# lens.net
KiCad netlist of a schematic drawn in EAGLE
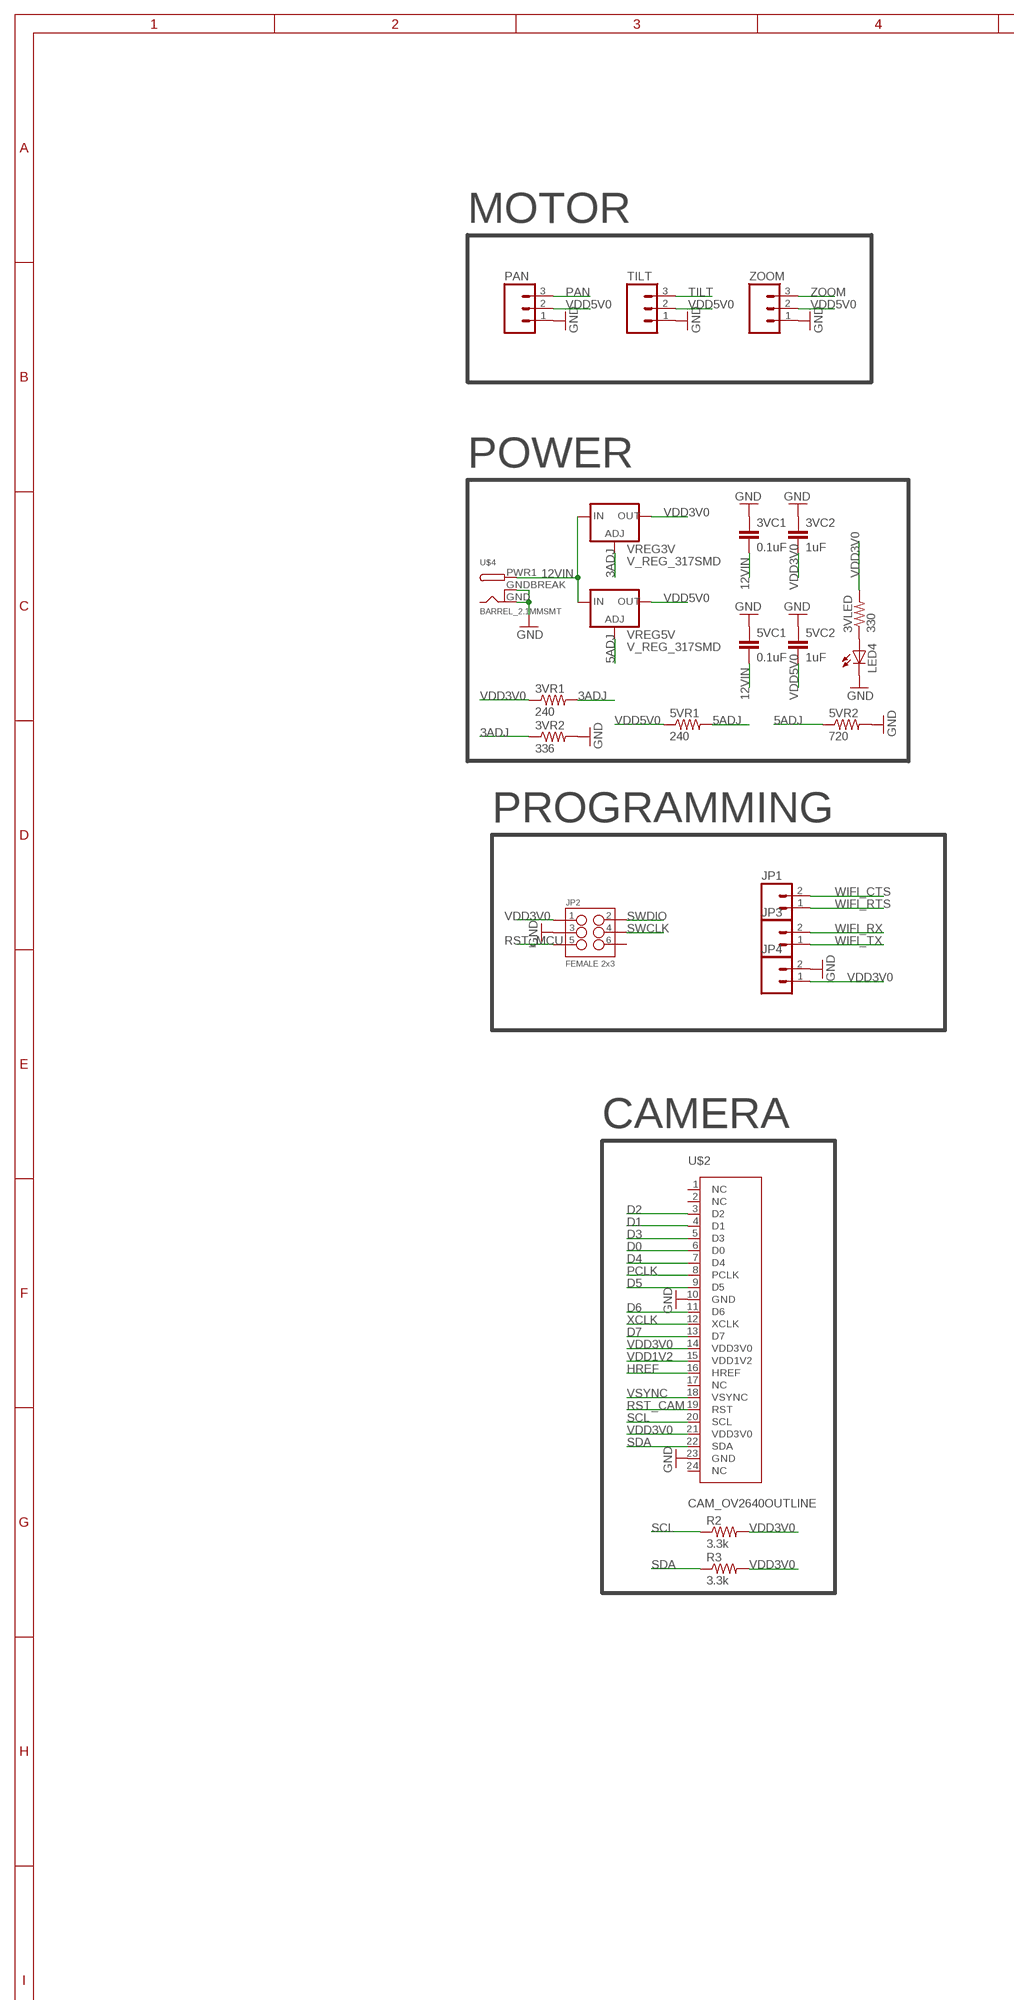
[diagram p0: schematic, sheet 1, part 1 of 2]
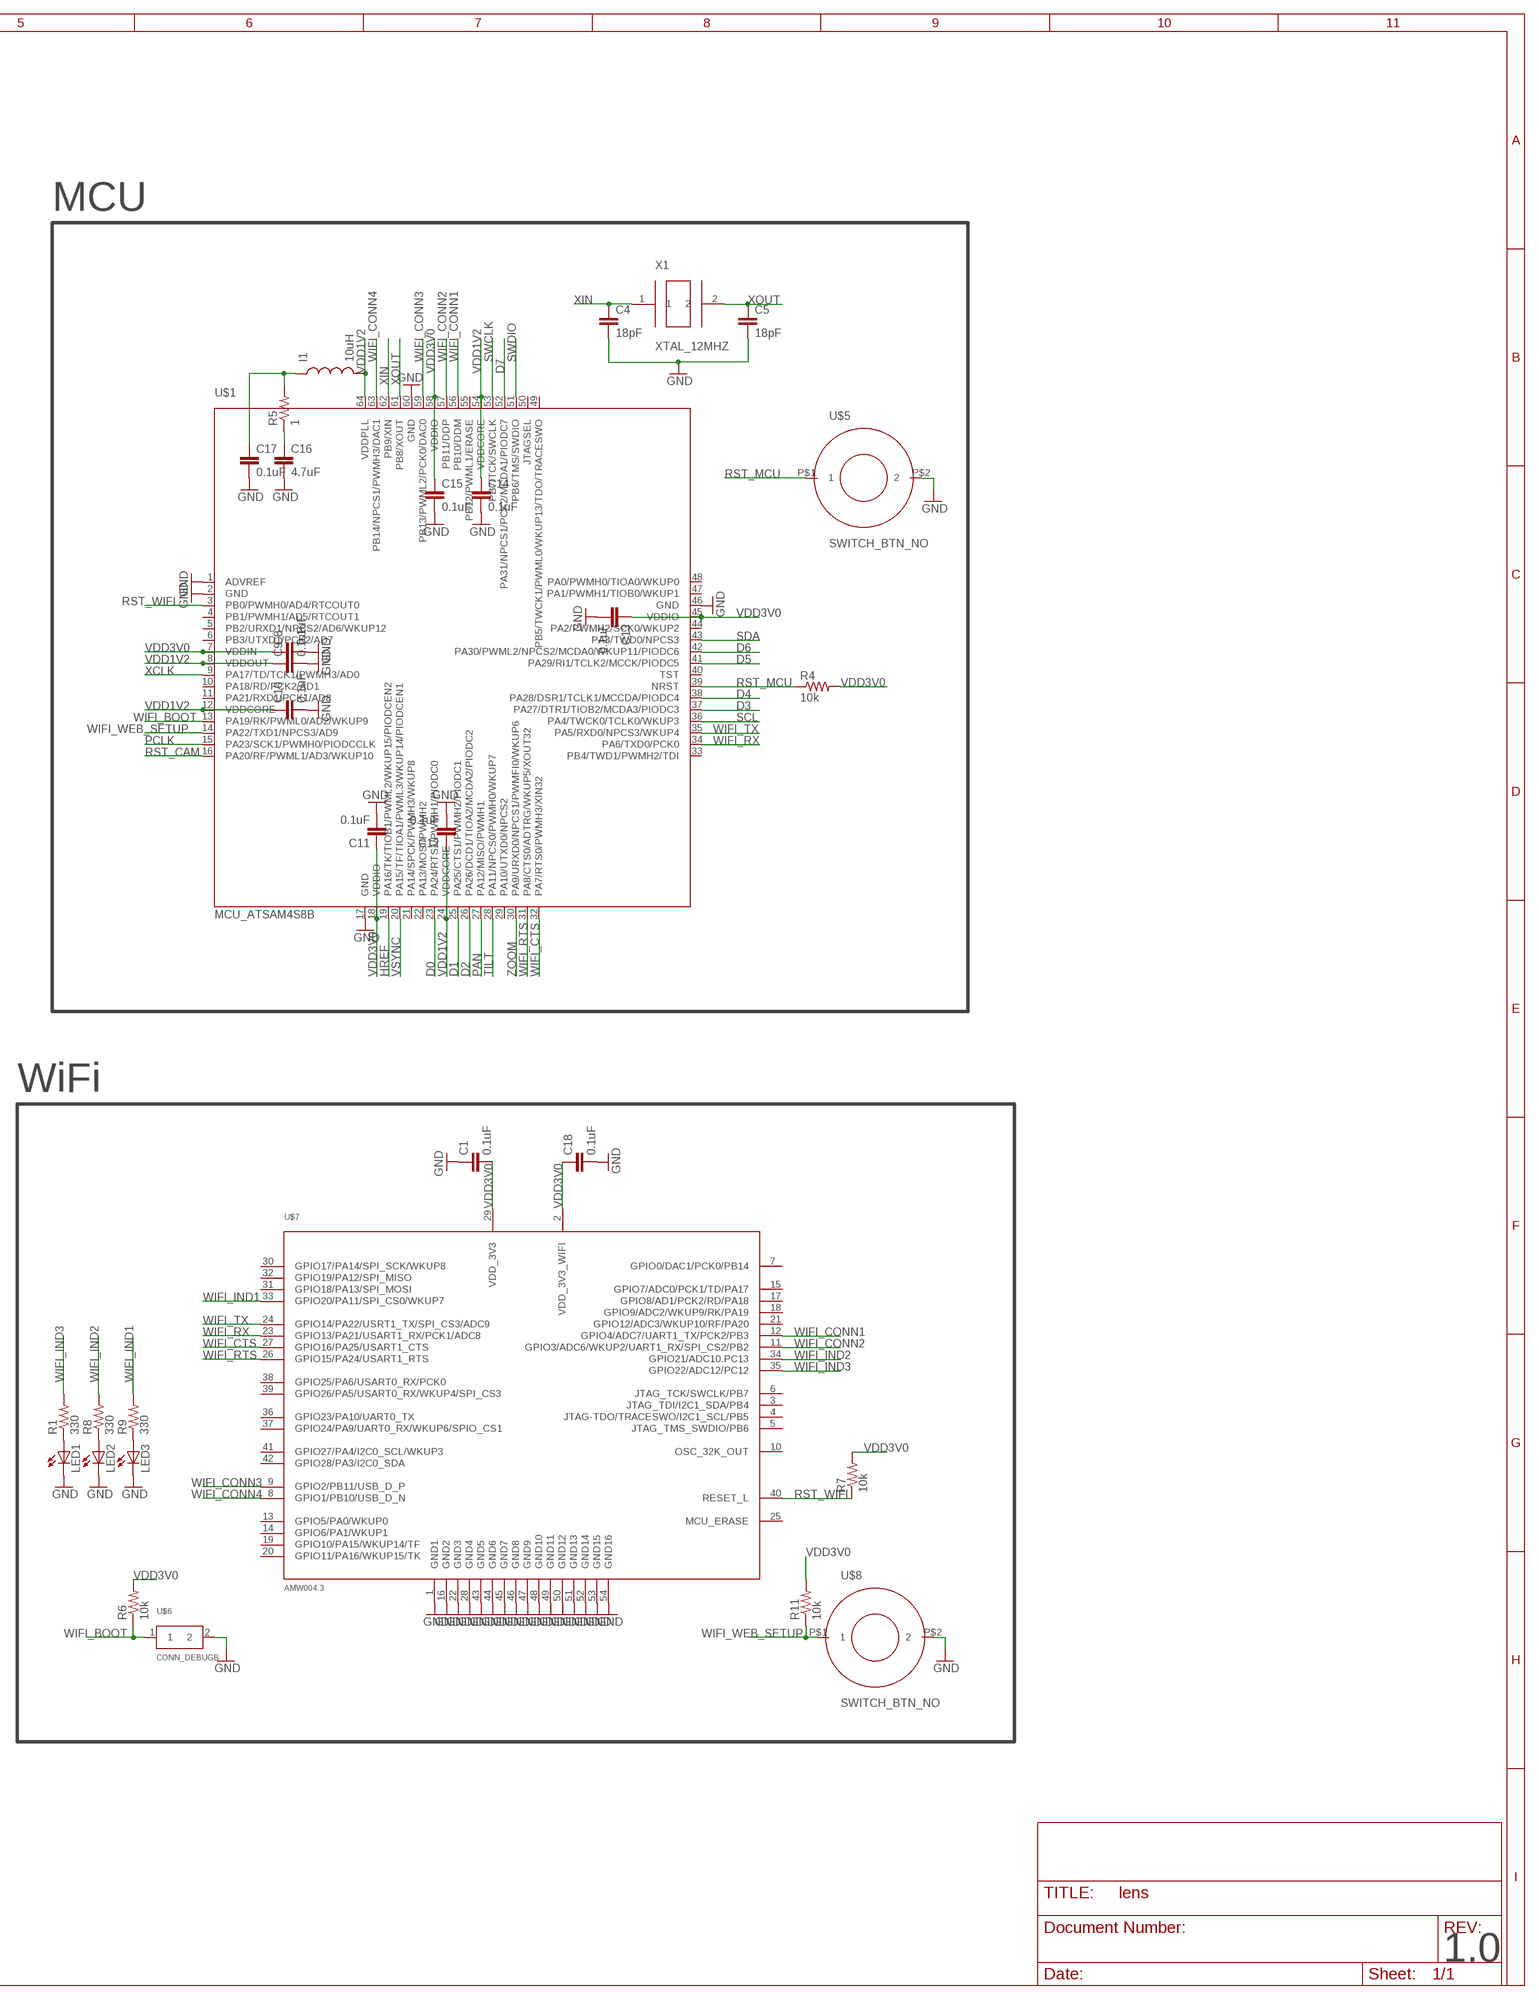
[diagram p1: schematic, sheet 1, part 2 of 2]

(export (version "E")
  (design (tool "Eeschema 10.0.6"))
  (components
    (comp (ref "3VC1")
      (value "0.1uF")
      (footprint "eagle-import:0805")
      (libsource (lib "eagle-import") (part "CAP"))
    )
    (comp (ref "3VC2")
      (value "1uF")
      (footprint "eagle-import:0805")
      (libsource (lib "eagle-import") (part "CAP"))
    )
    (comp (ref "3VLED")
      (value "330")
      (footprint "eagle-import:0805")
      (libsource (lib "eagle-import") (part "RES"))
    )
    (comp (ref "3VR1")
      (value "240")
      (footprint "eagle-import:0805")
      (libsource (lib "eagle-import") (part "RES"))
    )
    (comp (ref "3VR2")
      (value "336")
      (footprint "eagle-import:0805")
      (libsource (lib "eagle-import") (part "RES"))
    )
    (comp (ref "5VC1")
      (value "0.1uF")
      (footprint "eagle-import:0805")
      (libsource (lib "eagle-import") (part "CAP"))
    )
    (comp (ref "5VC2")
      (value "1uF")
      (footprint "eagle-import:0805")
      (libsource (lib "eagle-import") (part "CAP"))
    )
    (comp (ref "5VR1")
      (value "240")
      (footprint "eagle-import:0805")
      (libsource (lib "eagle-import") (part "RES"))
    )
    (comp (ref "5VR2")
      (value "720")
      (footprint "eagle-import:0805")
      (libsource (lib "eagle-import") (part "RES"))
    )
    (comp (ref "C1")
      (value "0.1uF")
      (footprint "eagle-import:0805")
      (libsource (lib "eagle-import") (part "CAP"))
    )
    (comp (ref "C4")
      (value "18pF")
      (footprint "eagle-import:0805")
      (libsource (lib "eagle-import") (part "CAP"))
    )
    (comp (ref "C5")
      (value "18pF")
      (footprint "eagle-import:0805")
      (libsource (lib "eagle-import") (part "CAP"))
    )
    (comp (ref "C8")
      (value "0.1uF")
      (footprint "eagle-import:0805")
      (libsource (lib "eagle-import") (part "CAP"))
    )
    (comp (ref "C9")
      (value "0.1uF")
      (footprint "eagle-import:0805")
      (libsource (lib "eagle-import") (part "CAP"))
    )
    (comp (ref "C10")
      (value "0.1uF")
      (footprint "eagle-import:0805")
      (libsource (lib "eagle-import") (part "CAP"))
    )
    (comp (ref "C11")
      (value "0.1uF")
      (footprint "eagle-import:0805")
      (libsource (lib "eagle-import") (part "CAP"))
    )
    (comp (ref "C12")
      (value "0.1uF")
      (footprint "eagle-import:0805")
      (libsource (lib "eagle-import") (part "CAP"))
    )
    (comp (ref "C13")
      (value "0.1uF")
      (footprint "eagle-import:0805")
      (libsource (lib "eagle-import") (part "CAP"))
    )
    (comp (ref "C14")
      (value "0.1uF")
      (footprint "eagle-import:0805")
      (libsource (lib "eagle-import") (part "CAP"))
    )
    (comp (ref "C15")
      (value "0.1uF")
      (footprint "eagle-import:0805")
      (libsource (lib "eagle-import") (part "CAP"))
    )
    (comp (ref "C16")
      (value "4.7uF")
      (footprint "eagle-import:0805")
      (libsource (lib "eagle-import") (part "CAP"))
    )
    (comp (ref "C17")
      (value "0.1uF")
      (footprint "eagle-import:0805")
      (libsource (lib "eagle-import") (part "CAP"))
    )
    (comp (ref "C18")
      (value "0.1uF")
      (footprint "eagle-import:0805")
      (libsource (lib "eagle-import") (part "CAP"))
    )
    (comp (ref "I1")
      (value "10uH")
      (footprint "eagle-import:0805")
      (libsource (lib "eagle-import") (part "IND"))
    )
    (comp (ref "JP1")
      (value "M02PTH")
      (footprint "eagle-import:1X02")
      (libsource (lib "eagle-import") (part "M02PTH"))
    )
    (comp (ref "JP2")
      (value "FEMALE 2x3")
      (footprint "eagle-import:2X3")
      (libsource (lib "eagle-import") (part "M03X2FEMALE"))
    )
    (comp (ref "JP3")
      (value "M02PTH")
      (footprint "eagle-import:1X02")
      (libsource (lib "eagle-import") (part "M02PTH"))
    )
    (comp (ref "JP4")
      (value "M02PTH")
      (footprint "eagle-import:1X02")
      (libsource (lib "eagle-import") (part "M02PTH"))
    )
    (comp (ref "LED1")
      (value "LED0603")
      (footprint "eagle-import:LED-0603")
      (libsource (lib "eagle-import") (part "LED0603"))
    )
    (comp (ref "LED2")
      (value "LED0603")
      (footprint "eagle-import:LED-0603")
      (libsource (lib "eagle-import") (part "LED0603"))
    )
    (comp (ref "LED3")
      (value "LED0603")
      (footprint "eagle-import:LED-0603")
      (libsource (lib "eagle-import") (part "LED0603"))
    )
    (comp (ref "LED4")
      (value "LED0603")
      (footprint "eagle-import:LED-0603")
      (libsource (lib "eagle-import") (part "LED0603"))
    )
    (comp (ref "PAN")
      (value "M03PTH")
      (footprint "eagle-import:1X03")
      (libsource (lib "eagle-import") (part "M03PTH"))
    )
    (comp (ref "R1")
      (value "330")
      (footprint "eagle-import:0805")
      (libsource (lib "eagle-import") (part "RES"))
    )
    (comp (ref "R2")
      (value "3.3k")
      (footprint "eagle-import:0805")
      (libsource (lib "eagle-import") (part "RES"))
    )
    (comp (ref "R3")
      (value "3.3k")
      (footprint "eagle-import:0805")
      (libsource (lib "eagle-import") (part "RES"))
    )
    (comp (ref "R4")
      (value "10k")
      (footprint "eagle-import:0805")
      (libsource (lib "eagle-import") (part "RES"))
    )
    (comp (ref "R5")
      (value "1")
      (footprint "eagle-import:0805")
      (libsource (lib "eagle-import") (part "RES"))
    )
    (comp (ref "R6")
      (value "10k")
      (footprint "eagle-import:0805")
      (libsource (lib "eagle-import") (part "RES"))
    )
    (comp (ref "R7")
      (value "10k")
      (footprint "eagle-import:0805")
      (libsource (lib "eagle-import") (part "RES"))
    )
    (comp (ref "R8")
      (value "330")
      (footprint "eagle-import:0805")
      (libsource (lib "eagle-import") (part "RES"))
    )
    (comp (ref "R9")
      (value "330")
      (footprint "eagle-import:0805")
      (libsource (lib "eagle-import") (part "RES"))
    )
    (comp (ref "R11")
      (value "10k")
      (footprint "eagle-import:0805")
      (libsource (lib "eagle-import") (part "RES"))
    )
    (comp (ref "TILT")
      (value "M03PTH")
      (footprint "eagle-import:1X03")
      (libsource (lib "eagle-import") (part "M03PTH"))
    )
    (comp (ref "U$1")
      (value "MCU_ATSAM4S8B")
      (footprint "eagle-import:QFP50P1200X1200X160-64N")
      (libsource (lib "eagle-import") (part "MCU_ATSAM4S8B"))
    )
    (comp (ref "U$2")
      (value "CAM_OV2640OUTLINE")
      (footprint "eagle-import:CAM_CONN")
      (libsource (lib "eagle-import") (part "CAM_OV2640OUTLINE"))
    )
    (comp (ref "U$4")
      (value "BARREL_2.1MMSMT")
      (footprint "eagle-import:DCJACK_2MM_SMT")
      (libsource (lib "eagle-import") (part "BARREL_2.1MMSMT"))
    )
    (comp (ref "U$5")
      (value "SWITCH_BTN_NO")
      (footprint "eagle-import:BTN_2")
      (libsource (lib "eagle-import") (part "SWITCH_BTN_NO"))
    )
    (comp (ref "U$6")
      (value "CONN_DEBUGB")
      (footprint "eagle-import:1X2_SMALL_SMD")
      (libsource (lib "eagle-import") (part "CONN_DEBUGB"))
    )
    (comp (ref "U$7")
      (value "AMW004.3")
      (footprint "eagle-import:AMW004")
      (libsource (lib "eagle-import") (part "AMW004.3"))
    )
    (comp (ref "U$8")
      (value "SWITCH_BTN_NO")
      (footprint "eagle-import:BTN_2")
      (libsource (lib "eagle-import") (part "SWITCH_BTN_NO"))
    )
    (comp (ref "VREG3V")
      (value "V_REG_317SMD")
      (footprint "eagle-import:SOT223")
      (libsource (lib "eagle-import") (part "V_REG_317SMD"))
    )
    (comp (ref "VREG5V")
      (value "V_REG_317SMD")
      (footprint "eagle-import:SOT223")
      (libsource (lib "eagle-import") (part "V_REG_317SMD"))
    )
    (comp (ref "X1")
      (value "XTAL_12MHZ")
      (footprint "eagle-import:ABM7-16.000MHZ-D2Y-T")
      (libsource (lib "eagle-import") (part "XTAL_12MHZ"))
    )
    (comp (ref "ZOOM")
      (value "M03PTH")
      (footprint "eagle-import:1X03")
      (libsource (lib "eagle-import") (part "M03PTH"))
    )
  )
  (nets
    (net (code "1") (name "/3ADJ") (class "Default")
      (node (ref "3VR1") (pin "2") (pinfunction "2_2") (pintype "passive"))
      (node (ref "3VR2") (pin "1") (pinfunction "1_1") (pintype "passive"))
      (node (ref "VREG3V") (pin "1") (pinfunction "ADJ_1") (pintype "input"))
    )
    (net (code "2") (name "/5ADJ") (class "Default")
      (node (ref "5VR1") (pin "2") (pinfunction "2_2") (pintype "passive"))
      (node (ref "5VR2") (pin "1") (pinfunction "1_1") (pintype "passive"))
      (node (ref "VREG5V") (pin "1") (pinfunction "ADJ_1") (pintype "input"))
    )
    (net (code "3") (name "/12VIN") (class "Default")
      (node (ref "3VC1") (pin "2") (pinfunction "2_2") (pintype "passive"))
      (node (ref "5VC1") (pin "2") (pinfunction "2_2") (pintype "passive"))
      (node (ref "U$4") (pin "PWR1") (pinfunction "PWR_PWR1") (pintype "power_in"))
      (node (ref "VREG3V") (pin "3") (pinfunction "IN_3") (pintype "input"))
      (node (ref "VREG5V") (pin "3") (pinfunction "IN_3") (pintype "input"))
    )
    (net (code "4") (name "/D0") (class "Default")
      (node (ref "U$1") (pin "23") (pinfunction "PA24/RTS1/PWMH1/PIODC0_23") (pintype "bidirectional"))
      (node (ref "U$2") (pin "6") (pinfunction "D0_6") (pintype "bidirectional"))
    )
    (net (code "5") (name "/D1") (class "Default")
      (node (ref "U$1") (pin "25") (pinfunction "PA25/CTS1/PWMH2/PIODC1_25") (pintype "bidirectional"))
      (node (ref "U$2") (pin "4") (pinfunction "D1_4") (pintype "bidirectional"))
    )
    (net (code "6") (name "/D2") (class "Default")
      (node (ref "U$1") (pin "26") (pinfunction "PA26/DCD1/TIOA2/MCDA2/PIODC2_26") (pintype "bidirectional"))
      (node (ref "U$2") (pin "3") (pinfunction "D2_3") (pintype "bidirectional"))
    )
    (net (code "7") (name "/D3") (class "Default")
      (node (ref "U$1") (pin "37") (pinfunction "PA27/DTR1/TIOB2/MCDA3/PIODC3_37") (pintype "bidirectional"))
      (node (ref "U$2") (pin "5") (pinfunction "D3_5") (pintype "bidirectional"))
    )
    (net (code "8") (name "/D4") (class "Default")
      (node (ref "U$1") (pin "38") (pinfunction "PA28/DSR1/TCLK1/MCCDA/PIODC4_38") (pintype "bidirectional"))
      (node (ref "U$2") (pin "7") (pinfunction "D4_7") (pintype "bidirectional"))
    )
    (net (code "9") (name "/D5") (class "Default")
      (node (ref "U$1") (pin "41") (pinfunction "PA29/RI1/TCLK2/MCCK/PIODC5_41") (pintype "bidirectional"))
      (node (ref "U$2") (pin "9") (pinfunction "D5_9") (pintype "bidirectional"))
    )
    (net (code "10") (name "/D6") (class "Default")
      (node (ref "U$1") (pin "42") (pinfunction "PA30/PWML2/NPCS2/MCDA0/WKUP11/PIODC6_42") (pintype "bidirectional"))
      (node (ref "U$2") (pin "11") (pinfunction "D6_11") (pintype "bidirectional"))
    )
    (net (code "11") (name "/D7") (class "Default")
      (node (ref "U$1") (pin "52") (pinfunction "PA31/NPCS1/PCK2/MCDA1/PIODC7_52") (pintype "bidirectional"))
      (node (ref "U$2") (pin "13") (pinfunction "D7_13") (pintype "bidirectional"))
    )
    (net (code "12") (name "/HREF") (class "Default")
      (node (ref "U$1") (pin "19") (pinfunction "PA16/TK/TIOB1/PWML2/WKUP15/PIODCEN2_19") (pintype "bidirectional"))
      (node (ref "U$2") (pin "16") (pinfunction "HREF_16") (pintype "bidirectional"))
    )
    (net (code "13") (name "/PAN") (class "Default")
      (node (ref "PAN") (pin "3") (pinfunction "3_3") (pintype "passive"))
      (node (ref "U$1") (pin "27") (pinfunction "PA12/MISO/PWMH1_27") (pintype "bidirectional"))
    )
    (net (code "14") (name "/PCLK") (class "Default")
      (node (ref "U$1") (pin "15") (pinfunction "PA23/SCK1/PWMH0/PIODCCLK_15") (pintype "bidirectional"))
      (node (ref "U$2") (pin "8") (pinfunction "PCLK_8") (pintype "bidirectional"))
    )
    (net (code "15") (name "/RST_CAM") (class "Default")
      (node (ref "U$1") (pin "16") (pinfunction "PA20/RF/PWML1/AD3/WKUP10_16") (pintype "bidirectional"))
      (node (ref "U$2") (pin "19") (pinfunction "RST_19") (pintype "bidirectional"))
    )
    (net (code "16") (name "/RST_MCU") (class "Default")
      (node (ref "JP2") (pin "5") (pinfunction "5_5") (pintype "bidirectional"))
      (node (ref "R4") (pin "1") (pinfunction "1_1") (pintype "passive"))
      (node (ref "U$1") (pin "39") (pinfunction "NRST_39") (pintype "bidirectional"))
      (node (ref "U$5") (pin "P$1") (pinfunction "1_P$1") (pintype "bidirectional"))
    )
    (net (code "17") (name "/RST_WIFI") (class "Default")
      (node (ref "R7") (pin "1") (pinfunction "1_1") (pintype "passive"))
      (node (ref "U$1") (pin "3") (pinfunction "PB0/PWMH0/AD4/RTCOUT0_3") (pintype "bidirectional"))
      (node (ref "U$7") (pin "40") (pinfunction "RESET_L_40") (pintype "bidirectional"))
    )
    (net (code "18") (name "/SCL") (class "Default")
      (node (ref "R2") (pin "1") (pinfunction "1_1") (pintype "passive"))
      (node (ref "U$1") (pin "36") (pinfunction "PA4/TWCK0/TCLK0/WKUP3_36") (pintype "bidirectional"))
      (node (ref "U$2") (pin "20") (pinfunction "SCL_20") (pintype "bidirectional"))
    )
    (net (code "19") (name "/SDA") (class "Default")
      (node (ref "R3") (pin "1") (pinfunction "1_1") (pintype "passive"))
      (node (ref "U$1") (pin "43") (pinfunction "PA3/TWD0/NPCS3_43") (pintype "bidirectional"))
      (node (ref "U$2") (pin "22") (pinfunction "SDA_22") (pintype "bidirectional"))
    )
    (net (code "20") (name "/SWCLK") (class "Default")
      (node (ref "JP2") (pin "4") (pinfunction "4_4") (pintype "bidirectional"))
      (node (ref "U$1") (pin "53") (pinfunction "PB7/TCK/SWCLK_53") (pintype "bidirectional"))
    )
    (net (code "21") (name "/SWDIO") (class "Default")
      (node (ref "JP2") (pin "2") (pinfunction "2_2") (pintype "bidirectional"))
      (node (ref "U$1") (pin "51") (pinfunction "PB6/TMS/SWDIO_51") (pintype "bidirectional"))
    )
    (net (code "22") (name "/TILT") (class "Default")
      (node (ref "TILT") (pin "3") (pinfunction "3_3") (pintype "passive"))
      (node (ref "U$1") (pin "28") (pinfunction "PA11/NPCS0/PWMH0/WKUP7_28") (pintype "bidirectional"))
    )
    (net (code "23") (name "/VDD1V2") (class "Default")
      (node (ref "C10") (pin "1") (pinfunction "1_1") (pintype "passive"))
      (node (ref "C12") (pin "1") (pinfunction "1_1") (pintype "passive"))
      (node (ref "C14") (pin "1") (pinfunction "1_1") (pintype "passive"))
      (node (ref "C9") (pin "1") (pinfunction "1_1") (pintype "passive"))
      (node (ref "I1") (pin "2") (pinfunction "2_2") (pintype "passive"))
      (node (ref "U$1") (pin "12") (pinfunction "VDDCORE_12") (pintype "bidirectional"))
      (node (ref "U$1") (pin "24") (pinfunction "VDDCORE_24") (pintype "bidirectional"))
      (node (ref "U$1") (pin "54") (pinfunction "VDDCORE_54") (pintype "bidirectional"))
      (node (ref "U$1") (pin "64") (pinfunction "VDDPLL_64") (pintype "bidirectional"))
      (node (ref "U$1") (pin "8") (pinfunction "VDDOUT_8") (pintype "bidirectional"))
      (node (ref "U$2") (pin "15") (pinfunction "VDD1V2_15") (pintype "bidirectional"))
    )
    (net (code "24") (name "/VDD3V0") (class "Default")
      (node (ref "3VC2") (pin "2") (pinfunction "2_2") (pintype "passive"))
      (node (ref "3VLED") (pin "2") (pinfunction "2_2") (pintype "passive"))
      (node (ref "3VR1") (pin "1") (pinfunction "1_1") (pintype "passive"))
      (node (ref "C1") (pin "2") (pinfunction "2_2") (pintype "passive"))
      (node (ref "C11") (pin "1") (pinfunction "1_1") (pintype "passive"))
      (node (ref "C13") (pin "1") (pinfunction "1_1") (pintype "passive"))
      (node (ref "C15") (pin "1") (pinfunction "1_1") (pintype "passive"))
      (node (ref "C18") (pin "1") (pinfunction "1_1") (pintype "passive"))
      (node (ref "C8") (pin "1") (pinfunction "1_1") (pintype "passive"))
      (node (ref "JP2") (pin "1") (pinfunction "1_1") (pintype "bidirectional"))
      (node (ref "JP4") (pin "1") (pinfunction "1_1") (pintype "passive"))
      (node (ref "R11") (pin "2") (pinfunction "2_2") (pintype "passive"))
      (node (ref "R2") (pin "2") (pinfunction "2_2") (pintype "passive"))
      (node (ref "R3") (pin "2") (pinfunction "2_2") (pintype "passive"))
      (node (ref "R4") (pin "2") (pinfunction "2_2") (pintype "passive"))
      (node (ref "R6") (pin "2") (pinfunction "2_2") (pintype "passive"))
      (node (ref "R7") (pin "2") (pinfunction "2_2") (pintype "passive"))
      (node (ref "U$1") (pin "18") (pinfunction "VDDIO_18") (pintype "bidirectional"))
      (node (ref "U$1") (pin "45") (pinfunction "VDDIO_45") (pintype "bidirectional"))
      (node (ref "U$1") (pin "58") (pinfunction "VDDIO_58") (pintype "bidirectional"))
      (node (ref "U$1") (pin "7") (pinfunction "VDDIN_7") (pintype "bidirectional"))
      (node (ref "U$2") (pin "14") (pinfunction "VDD3V0_14") (pintype "bidirectional"))
      (node (ref "U$2") (pin "21") (pinfunction "VDD3V0_21") (pintype "bidirectional"))
      (node (ref "U$7") (pin "2") (pinfunction "VDD_3V3_WIFI_2") (pintype "bidirectional"))
      (node (ref "U$7") (pin "29") (pinfunction "VDD_3V3_29") (pintype "bidirectional"))
      (node (ref "VREG3V") (pin "2") (pinfunction "OUT_2") (pintype "output"))
    )
    (net (code "25") (name "/VDD5V0") (class "Default")
      (node (ref "5VC2") (pin "2") (pinfunction "2_2") (pintype "passive"))
      (node (ref "5VR1") (pin "1") (pinfunction "1_1") (pintype "passive"))
      (node (ref "PAN") (pin "2") (pinfunction "2_2") (pintype "passive"))
      (node (ref "TILT") (pin "2") (pinfunction "2_2") (pintype "passive"))
      (node (ref "VREG5V") (pin "2") (pinfunction "OUT_2") (pintype "output"))
      (node (ref "ZOOM") (pin "2") (pinfunction "2_2") (pintype "passive"))
    )
    (net (code "26") (name "/VSYNC") (class "Default")
      (node (ref "U$1") (pin "20") (pinfunction "PA15/TF/TIOA1/PWML3/WKUP14/PIODCEN1_20") (pintype "bidirectional"))
      (node (ref "U$2") (pin "18") (pinfunction "VSYNC_18") (pintype "bidirectional"))
    )
    (net (code "27") (name "/WIFI_BOOT") (class "Default")
      (node (ref "R6") (pin "1") (pinfunction "1_1") (pintype "passive"))
      (node (ref "U$1") (pin "13") (pinfunction "PA19/RK/PWML0/AD2/WKUP9_13") (pintype "bidirectional"))
      (node (ref "U$6") (pin "1") (pinfunction "1_1") (pintype "bidirectional"))
    )
    (net (code "28") (name "/WIFI_CONN1") (class "Default")
      (node (ref "U$1") (pin "56") (pinfunction "PB10/DDM_56") (pintype "bidirectional"))
      (node (ref "U$7") (pin "12") (pinfunction "GPIO4/ADC7/UART1_TX/PCK2/PB3_12") (pintype "bidirectional"))
    )
    (net (code "29") (name "/WIFI_CONN2") (class "Default")
      (node (ref "U$1") (pin "57") (pinfunction "PB11/DDP_57") (pintype "bidirectional"))
      (node (ref "U$7") (pin "11") (pinfunction "GPIO3/ADC6/WKUP2/UART1_RX/SPI_CS2/PB2_11") (pintype "bidirectional"))
    )
    (net (code "30") (name "/WIFI_CONN3") (class "Default")
      (node (ref "U$1") (pin "59") (pinfunction "PB13/PWML2/PCK0/DAC0_59") (pintype "bidirectional"))
      (node (ref "U$7") (pin "9") (pinfunction "GPIO2/PB11/USB_D_P_9") (pintype "bidirectional"))
    )
    (net (code "31") (name "/WIFI_CONN4") (class "Default")
      (node (ref "U$1") (pin "63") (pinfunction "PB14/NPCS1/PWMH3/DAC1_63") (pintype "bidirectional"))
      (node (ref "U$7") (pin "8") (pinfunction "GPIO1/PB10/USB_D_N_8") (pintype "bidirectional"))
    )
    (net (code "32") (name "/WIFI_CTS") (class "Default")
      (node (ref "JP1") (pin "2") (pinfunction "2_2") (pintype "passive"))
      (node (ref "U$1") (pin "32") (pinfunction "PA7/RTS0/PWMH3/XIN32_32") (pintype "bidirectional"))
      (node (ref "U$7") (pin "27") (pinfunction "GPIO16/PA25/USART1_CTS_27") (pintype "bidirectional"))
    )
    (net (code "33") (name "/WIFI_IND1") (class "Default")
      (node (ref "R9") (pin "2") (pinfunction "2_2") (pintype "passive"))
      (node (ref "U$7") (pin "33") (pinfunction "GPIO20/PA11/SPI_CS0/WKUP7_33") (pintype "bidirectional"))
    )
    (net (code "34") (name "/WIFI_IND2") (class "Default")
      (node (ref "R8") (pin "2") (pinfunction "2_2") (pintype "passive"))
      (node (ref "U$7") (pin "34") (pinfunction "GPIO21/ADC10.PC13_34") (pintype "bidirectional"))
    )
    (net (code "35") (name "/WIFI_IND3") (class "Default")
      (node (ref "R1") (pin "2") (pinfunction "2_2") (pintype "passive"))
      (node (ref "U$7") (pin "35") (pinfunction "GPIO22/ADC12/PC12_35") (pintype "bidirectional"))
    )
    (net (code "36") (name "/WIFI_RTS") (class "Default")
      (node (ref "JP1") (pin "1") (pinfunction "1_1") (pintype "passive"))
      (node (ref "U$1") (pin "31") (pinfunction "PA8/CTS0/ADTRG/WKUP5/XOUT32_31") (pintype "bidirectional"))
      (node (ref "U$7") (pin "26") (pinfunction "GPIO15/PA24/USART1_RTS_26") (pintype "bidirectional"))
    )
    (net (code "37") (name "/WIFI_RX") (class "Default")
      (node (ref "JP3") (pin "2") (pinfunction "2_2") (pintype "passive"))
      (node (ref "U$1") (pin "34") (pinfunction "PA6/TXD0/PCK0_34") (pintype "bidirectional"))
      (node (ref "U$7") (pin "23") (pinfunction "GPIO13/PA21/USART1_RX/PCK1/ADC8_23") (pintype "bidirectional"))
    )
    (net (code "38") (name "/WIFI_TX") (class "Default")
      (node (ref "JP3") (pin "1") (pinfunction "1_1") (pintype "passive"))
      (node (ref "U$1") (pin "35") (pinfunction "PA5/RXD0/NPCS3/WKUP4_35") (pintype "bidirectional"))
      (node (ref "U$7") (pin "24") (pinfunction "GPIO14/PA22/USRT1_TX/SPI_CS3/ADC9_24") (pintype "bidirectional"))
    )
    (net (code "39") (name "/WIFI_WEB_SETUP") (class "Default")
      (node (ref "R11") (pin "1") (pinfunction "1_1") (pintype "passive"))
      (node (ref "U$1") (pin "14") (pinfunction "PA22/TXD1/NPCS3/AD9_14") (pintype "bidirectional"))
      (node (ref "U$8") (pin "P$1") (pinfunction "1_P$1") (pintype "bidirectional"))
    )
    (net (code "40") (name "/XCLK") (class "Default")
      (node (ref "U$1") (pin "9") (pinfunction "PA17/TD/TCK1/PWMH3/AD0_9") (pintype "bidirectional"))
      (node (ref "U$2") (pin "12") (pinfunction "XCLK_12") (pintype "bidirectional"))
    )
    (net (code "41") (name "/XIN") (class "Default")
      (node (ref "C4") (pin "1") (pinfunction "1_1") (pintype "passive"))
      (node (ref "U$1") (pin "62") (pinfunction "PB9/XIN_62") (pintype "bidirectional"))
      (node (ref "X1") (pin "1") (pinfunction "1_1") (pintype "bidirectional"))
    )
    (net (code "42") (name "/XOUT") (class "Default")
      (node (ref "C5") (pin "1") (pinfunction "1_1") (pintype "passive"))
      (node (ref "U$1") (pin "61") (pinfunction "PB8/XOUT_61") (pintype "bidirectional"))
      (node (ref "X1") (pin "2") (pinfunction "2_2") (pintype "bidirectional"))
    )
    (net (code "43") (name "/ZOOM") (class "Default")
      (node (ref "U$1") (pin "30") (pinfunction "PA9/URXD0/NPCS1/PWMFI0/WKUP6_30") (pintype "bidirectional"))
      (node (ref "ZOOM") (pin "3") (pinfunction "3_3") (pintype "passive"))
    )
    (net (code "44") (name "GND") (class "Default")
      (node (ref "3VC1") (pin "1") (pinfunction "1_1") (pintype "passive"))
      (node (ref "3VC2") (pin "1") (pinfunction "1_1") (pintype "passive"))
      (node (ref "3VR2") (pin "2") (pinfunction "2_2") (pintype "passive"))
      (node (ref "5VC1") (pin "1") (pinfunction "1_1") (pintype "passive"))
      (node (ref "5VC2") (pin "1") (pinfunction "1_1") (pintype "passive"))
      (node (ref "5VR2") (pin "2") (pinfunction "2_2") (pintype "passive"))
      (node (ref "C1") (pin "1") (pinfunction "1_1") (pintype "passive"))
      (node (ref "C10") (pin "2") (pinfunction "2_2") (pintype "passive"))
      (node (ref "C11") (pin "2") (pinfunction "2_2") (pintype "passive"))
      (node (ref "C12") (pin "2") (pinfunction "2_2") (pintype "passive"))
      (node (ref "C13") (pin "2") (pinfunction "2_2") (pintype "passive"))
      (node (ref "C14") (pin "2") (pinfunction "2_2") (pintype "passive"))
      (node (ref "C15") (pin "2") (pinfunction "2_2") (pintype "passive"))
      (node (ref "C16") (pin "2") (pinfunction "2_2") (pintype "passive"))
      (node (ref "C17") (pin "2") (pinfunction "2_2") (pintype "passive"))
      (node (ref "C18") (pin "2") (pinfunction "2_2") (pintype "passive"))
      (node (ref "C4") (pin "2") (pinfunction "2_2") (pintype "passive"))
      (node (ref "C5") (pin "2") (pinfunction "2_2") (pintype "passive"))
      (node (ref "C8") (pin "2") (pinfunction "2_2") (pintype "passive"))
      (node (ref "C9") (pin "2") (pinfunction "2_2") (pintype "passive"))
      (node (ref "JP2") (pin "3") (pinfunction "3_3") (pintype "bidirectional"))
      (node (ref "JP4") (pin "2") (pinfunction "2_2") (pintype "passive"))
      (node (ref "LED1") (pin "C") (pinfunction "C_C") (pintype "passive"))
      (node (ref "LED2") (pin "C") (pinfunction "C_C") (pintype "passive"))
      (node (ref "LED3") (pin "C") (pinfunction "C_C") (pintype "passive"))
      (node (ref "LED4") (pin "C") (pinfunction "C_C") (pintype "passive"))
      (node (ref "PAN") (pin "1") (pinfunction "1_1") (pintype "passive"))
      (node (ref "TILT") (pin "1") (pinfunction "1_1") (pintype "passive"))
      (node (ref "U$1") (pin "1") (pinfunction "ADVREF_1") (pintype "bidirectional"))
      (node (ref "U$1") (pin "17") (pinfunction "GND_17") (pintype "bidirectional"))
      (node (ref "U$1") (pin "2") (pinfunction "GND_2") (pintype "bidirectional"))
      (node (ref "U$1") (pin "46") (pinfunction "GND_46") (pintype "bidirectional"))
      (node (ref "U$1") (pin "60") (pinfunction "GND_60") (pintype "bidirectional"))
      (node (ref "U$2") (pin "10") (pinfunction "GND_10") (pintype "bidirectional"))
      (node (ref "U$2") (pin "23") (pinfunction "GND_23") (pintype "bidirectional"))
      (node (ref "U$4") (pin "GND") (pinfunction "GND_GND") (pintype "power_in"))
      (node (ref "U$4") (pin "GNDBREAK") (pinfunction "GNDBREAK_GNDBREAK") (pintype "power_in"))
      (node (ref "U$5") (pin "P$2") (pinfunction "2_P$2") (pintype "bidirectional"))
      (node (ref "U$6") (pin "2") (pinfunction "2_2") (pintype "bidirectional"))
      (node (ref "U$7") (pin "1") (pinfunction "GND1_1") (pintype "power_in"))
      (node (ref "U$7") (pin "16") (pinfunction "GND2_16") (pintype "power_in"))
      (node (ref "U$7") (pin "22") (pinfunction "GND3_22") (pintype "power_in"))
      (node (ref "U$7") (pin "28") (pinfunction "GND4_28") (pintype "power_in"))
      (node (ref "U$7") (pin "43") (pinfunction "GND5_43") (pintype "power_in"))
      (node (ref "U$7") (pin "44") (pinfunction "GND6_44") (pintype "power_in"))
      (node (ref "U$7") (pin "45") (pinfunction "GND7_45") (pintype "power_in"))
      (node (ref "U$7") (pin "46") (pinfunction "GND8_46") (pintype "power_in"))
      (node (ref "U$7") (pin "47") (pinfunction "GND9_47") (pintype "power_in"))
      (node (ref "U$7") (pin "48") (pinfunction "GND10_48") (pintype "power_in"))
      (node (ref "U$7") (pin "49") (pinfunction "GND11_49") (pintype "power_in"))
      (node (ref "U$7") (pin "50") (pinfunction "GND12_50") (pintype "power_in"))
      (node (ref "U$7") (pin "51") (pinfunction "GND13_51") (pintype "power_in"))
      (node (ref "U$7") (pin "52") (pinfunction "GND14_52") (pintype "power_in"))
      (node (ref "U$7") (pin "53") (pinfunction "GND15_53") (pintype "power_in"))
      (node (ref "U$7") (pin "54") (pinfunction "GND16_54") (pintype "power_in"))
      (node (ref "U$8") (pin "P$2") (pinfunction "2_P$2") (pintype "bidirectional"))
      (node (ref "ZOOM") (pin "1") (pinfunction "1_1") (pintype "passive"))
    )
    (net (code "45") (name "Net-(3VLED-Pad1)") (class "Default")
      (node (ref "3VLED") (pin "1") (pinfunction "1_1") (pintype "passive"))
      (node (ref "LED4") (pin "A") (pinfunction "A_A") (pintype "passive"))
    )
    (net (code "46") (name "Net-(C16-Pad1)") (class "Default")
      (node (ref "C16") (pin "1") (pinfunction "1_1") (pintype "passive"))
      (node (ref "R5") (pin "1") (pinfunction "1_1") (pintype "passive"))
    )
    (net (code "47") (name "Net-(C17-Pad1)") (class "Default")
      (node (ref "C17") (pin "1") (pinfunction "1_1") (pintype "passive"))
      (node (ref "I1") (pin "1") (pinfunction "1_1") (pintype "passive"))
      (node (ref "R5") (pin "2") (pinfunction "2_2") (pintype "passive"))
    )
    (net (code "48") (name "Net-(LED1-PadA)") (class "Default")
      (node (ref "LED1") (pin "A") (pinfunction "A_A") (pintype "passive"))
      (node (ref "R1") (pin "1") (pinfunction "1_1") (pintype "passive"))
    )
    (net (code "49") (name "Net-(LED2-PadA)") (class "Default")
      (node (ref "LED2") (pin "A") (pinfunction "A_A") (pintype "passive"))
      (node (ref "R8") (pin "1") (pinfunction "1_1") (pintype "passive"))
    )
    (net (code "50") (name "Net-(LED3-PadA)") (class "Default")
      (node (ref "LED3") (pin "A") (pinfunction "A_A") (pintype "passive"))
      (node (ref "R9") (pin "1") (pinfunction "1_1") (pintype "passive"))
    )
    (net (code "51") (name "unconnected-(JP2-Pad6)") (class "Default")
      (node (ref "JP2") (pin "6") (pinfunction "6_6") (pintype "bidirectional"))
    )
    (net (code "52") (name "unconnected-(U$1-JTAGSEL-Pad50)") (class "Default")
      (node (ref "U$1") (pin "50") (pinfunction "JTAGSEL_50") (pintype "bidirectional"))
    )
    (net (code "53") (name "unconnected-(U$1-PA0{slash}PWMH0{slash}TIOA0{slash}WKUP0-Pad48)") (class "Default")
      (node (ref "U$1") (pin "48") (pinfunction "PA0/PWMH0/TIOA0/WKUP0_48") (pintype "bidirectional"))
    )
    (net (code "54") (name "unconnected-(U$1-PA1{slash}PWMH1{slash}TIOB0{slash}WKUP1-Pad47)") (class "Default")
      (node (ref "U$1") (pin "47") (pinfunction "PA1/PWMH1/TIOB0/WKUP1_47") (pintype "bidirectional"))
    )
    (net (code "55") (name "unconnected-(U$1-PA2{slash}PWMH2{slash}SCK0{slash}WKUP2-Pad44)") (class "Default")
      (node (ref "U$1") (pin "44") (pinfunction "PA2/PWMH2/SCK0/WKUP2_44") (pintype "bidirectional"))
    )
    (net (code "56") (name "unconnected-(U$1-PA10{slash}UTXD0{slash}NPCS2-Pad29)") (class "Default")
      (node (ref "U$1") (pin "29") (pinfunction "PA10/UTXD0/NPCS2_29") (pintype "bidirectional"))
    )
    (net (code "57") (name "unconnected-(U$1-PA13{slash}MOSI{slash}PWMH2-Pad22)") (class "Default")
      (node (ref "U$1") (pin "22") (pinfunction "PA13/MOSI/PWMH2_22") (pintype "bidirectional"))
    )
    (net (code "58") (name "unconnected-(U$1-PA14{slash}SPCK{slash}PWMH3{slash}WKUP8-Pad21)") (class "Default")
      (node (ref "U$1") (pin "21") (pinfunction "PA14/SPCK/PWMH3/WKUP8_21") (pintype "bidirectional"))
    )
    (net (code "59") (name "unconnected-(U$1-PA18{slash}RD{slash}PCK2{slash}AD1-Pad10)") (class "Default")
      (node (ref "U$1") (pin "10") (pinfunction "PA18/RD/PCK2/AD1_10") (pintype "bidirectional"))
    )
    (net (code "60") (name "unconnected-(U$1-PA21{slash}RXD1{slash}PCK1{slash}AD8-Pad11)") (class "Default")
      (node (ref "U$1") (pin "11") (pinfunction "PA21/RXD1/PCK1/AD8_11") (pintype "bidirectional"))
    )
    (net (code "61") (name "unconnected-(U$1-PB1{slash}PWMH1{slash}AD5{slash}RTCOUT1-Pad4)") (class "Default")
      (node (ref "U$1") (pin "4") (pinfunction "PB1/PWMH1/AD5/RTCOUT1_4") (pintype "bidirectional"))
    )
    (net (code "62") (name "unconnected-(U$1-PB2{slash}URXD1{slash}NPCS2{slash}AD6{slash}WKUP12-Pad5)") (class "Default")
      (node (ref "U$1") (pin "5") (pinfunction "PB2/URXD1/NPCS2/AD6/WKUP12_5") (pintype "bidirectional"))
    )
    (net (code "63") (name "unconnected-(U$1-PB3{slash}UTXD1{slash}PCK2{slash}AD7-Pad6)") (class "Default")
      (node (ref "U$1") (pin "6") (pinfunction "PB3/UTXD1/PCK2/AD7_6") (pintype "bidirectional"))
    )
    (net (code "64") (name "unconnected-(U$1-PB4{slash}TWD1{slash}PWMH2{slash}TDI-Pad33)") (class "Default")
      (node (ref "U$1") (pin "33") (pinfunction "PB4/TWD1/PWMH2/TDI_33") (pintype "bidirectional"))
    )
    (net (code "65") (name "unconnected-(U$1-PB5{slash}TWCK1{slash}PWML0{slash}WKUP13{slash}TDO{slash}TRACESWO-Pad49)") (class "Default")
      (node (ref "U$1") (pin "49") (pinfunction "PB5/TWCK1/PWML0/WKUP13/TDO/TRACESWO_49") (pintype "bidirectional"))
    )
    (net (code "66") (name "unconnected-(U$1-PB12{slash}PWML1{slash}ERASE-Pad55)") (class "Default")
      (node (ref "U$1") (pin "55") (pinfunction "PB12/PWML1/ERASE_55") (pintype "bidirectional"))
    )
    (net (code "67") (name "unconnected-(U$1-TST-Pad40)") (class "Default")
      (node (ref "U$1") (pin "40") (pinfunction "TST_40") (pintype "bidirectional"))
    )
    (net (code "68") (name "unconnected-(U$2-NC-Pad1)") (class "Default")
      (node (ref "U$2") (pin "1") (pinfunction "NC_1") (pintype "bidirectional"))
    )
    (net (code "69") (name "unconnected-(U$2-NC-Pad2)") (class "Default")
      (node (ref "U$2") (pin "2") (pinfunction "NC_2") (pintype "bidirectional"))
    )
    (net (code "70") (name "unconnected-(U$2-NC-Pad17)") (class "Default")
      (node (ref "U$2") (pin "17") (pinfunction "NC_17") (pintype "bidirectional"))
    )
    (net (code "71") (name "unconnected-(U$2-NC-Pad24)") (class "Default")
      (node (ref "U$2") (pin "24") (pinfunction "NC_24") (pintype "bidirectional"))
    )
    (net (code "72") (name "unconnected-(U$7-GPIO0{slash}DAC1{slash}PCK0{slash}PB14-Pad7)") (class "Default")
      (node (ref "U$7") (pin "7") (pinfunction "GPIO0/DAC1/PCK0/PB14_7") (pintype "bidirectional"))
    )
    (net (code "73") (name "unconnected-(U$7-GPIO5{slash}PA0{slash}WKUP0-Pad13)") (class "Default")
      (node (ref "U$7") (pin "13") (pinfunction "GPIO5/PA0/WKUP0_13") (pintype "bidirectional"))
    )
    (net (code "74") (name "unconnected-(U$7-GPIO6{slash}PA1{slash}WKUP1-Pad14)") (class "Default")
      (node (ref "U$7") (pin "14") (pinfunction "GPIO6/PA1/WKUP1_14") (pintype "bidirectional"))
    )
    (net (code "75") (name "unconnected-(U$7-GPIO7{slash}ADC0{slash}PCK1{slash}TD{slash}PA17-Pad15)") (class "Default")
      (node (ref "U$7") (pin "15") (pinfunction "GPIO7/ADC0/PCK1/TD/PA17_15") (pintype "bidirectional"))
    )
    (net (code "76") (name "unconnected-(U$7-GPIO8{slash}AD1{slash}PCK2{slash}RD{slash}PA18-Pad17)") (class "Default")
      (node (ref "U$7") (pin "17") (pinfunction "GPIO8/AD1/PCK2/RD/PA18_17") (pintype "bidirectional"))
    )
    (net (code "77") (name "unconnected-(U$7-GPIO9{slash}ADC2{slash}WKUP9{slash}RK{slash}PA19-Pad18)") (class "Default")
      (node (ref "U$7") (pin "18") (pinfunction "GPIO9/ADC2/WKUP9/RK/PA19_18") (pintype "bidirectional"))
    )
    (net (code "78") (name "unconnected-(U$7-GPIO10{slash}PA15{slash}WKUP14{slash}TF-Pad19)") (class "Default")
      (node (ref "U$7") (pin "19") (pinfunction "GPIO10/PA15/WKUP14/TF_19") (pintype "bidirectional"))
    )
    (net (code "79") (name "unconnected-(U$7-GPIO11{slash}PA16{slash}WKUP15{slash}TK-Pad20)") (class "Default")
      (node (ref "U$7") (pin "20") (pinfunction "GPIO11/PA16/WKUP15/TK_20") (pintype "bidirectional"))
    )
    (net (code "80") (name "unconnected-(U$7-GPIO12{slash}ADC3{slash}WKUP10{slash}RF{slash}PA20-Pad21)") (class "Default")
      (node (ref "U$7") (pin "21") (pinfunction "GPIO12/ADC3/WKUP10/RF/PA20_21") (pintype "bidirectional"))
    )
    (net (code "81") (name "unconnected-(U$7-GPIO17{slash}PA14{slash}SPI_SCK{slash}WKUP8-Pad30)") (class "Default")
      (node (ref "U$7") (pin "30") (pinfunction "GPIO17/PA14/SPI_SCK/WKUP8_30") (pintype "bidirectional"))
    )
    (net (code "82") (name "unconnected-(U$7-GPIO18{slash}PA13{slash}SPI_MOSI-Pad31)") (class "Default")
      (node (ref "U$7") (pin "31") (pinfunction "GPIO18/PA13/SPI_MOSI_31") (pintype "bidirectional"))
    )
    (net (code "83") (name "unconnected-(U$7-GPIO19{slash}PA12{slash}SPI_MISO-Pad32)") (class "Default")
      (node (ref "U$7") (pin "32") (pinfunction "GPIO19/PA12/SPI_MISO_32") (pintype "bidirectional"))
    )
    (net (code "84") (name "unconnected-(U$7-GPIO23{slash}PA10{slash}UART0_TX-Pad36)") (class "Default")
      (node (ref "U$7") (pin "36") (pinfunction "GPIO23/PA10/UART0_TX_36") (pintype "bidirectional"))
    )
    (net (code "85") (name "unconnected-(U$7-GPIO24{slash}PA9{slash}UART0_RX{slash}WKUP6{slash}SPIO_CS1-Pad37)") (class "Default")
      (node (ref "U$7") (pin "37") (pinfunction "GPIO24/PA9/UART0_RX/WKUP6/SPIO_CS1_37") (pintype "bidirectional"))
    )
    (net (code "86") (name "unconnected-(U$7-GPIO25{slash}PA6{slash}USART0_RX{slash}PCK0-Pad38)") (class "Default")
      (node (ref "U$7") (pin "38") (pinfunction "GPIO25/PA6/USART0_RX/PCK0_38") (pintype "bidirectional"))
    )
    (net (code "87") (name "unconnected-(U$7-GPIO26{slash}PA5{slash}USART0_RX{slash}WKUP4{slash}SPI_CS3-Pad39)") (class "Default")
      (node (ref "U$7") (pin "39") (pinfunction "GPIO26/PA5/USART0_RX/WKUP4/SPI_CS3_39") (pintype "bidirectional"))
    )
    (net (code "88") (name "unconnected-(U$7-GPIO27{slash}PA4{slash}I2C0_SCL{slash}WKUP3-Pad41)") (class "Default")
      (node (ref "U$7") (pin "41") (pinfunction "GPIO27/PA4/I2C0_SCL/WKUP3_41") (pintype "bidirectional"))
    )
    (net (code "89") (name "unconnected-(U$7-GPIO28{slash}PA3{slash}I2C0_SDA-Pad42)") (class "Default")
      (node (ref "U$7") (pin "42") (pinfunction "GPIO28/PA3/I2C0_SDA_42") (pintype "bidirectional"))
    )
    (net (code "90") (name "unconnected-(U$7-JTAG-TDO{slash}TRACESWO{slash}I2C1_SCL{slash}PB5-Pad4)") (class "Default")
      (node (ref "U$7") (pin "4") (pinfunction "JTAG-TDO/TRACESWO/I2C1_SCL/PB5_4") (pintype "bidirectional"))
    )
    (net (code "91") (name "unconnected-(U$7-JTAG_TCK{slash}SWCLK{slash}PB7-Pad6)") (class "Default")
      (node (ref "U$7") (pin "6") (pinfunction "JTAG_TCK/SWCLK/PB7_6") (pintype "bidirectional"))
    )
    (net (code "92") (name "unconnected-(U$7-JTAG_TDI{slash}I2C1_SDA{slash}PB4-Pad3)") (class "Default")
      (node (ref "U$7") (pin "3") (pinfunction "JTAG_TDI/I2C1_SDA/PB4_3") (pintype "bidirectional"))
    )
    (net (code "93") (name "unconnected-(U$7-JTAG_TMS_SWDIO{slash}PB6-Pad5)") (class "Default")
      (node (ref "U$7") (pin "5") (pinfunction "JTAG_TMS_SWDIO/PB6_5") (pintype "bidirectional"))
    )
    (net (code "94") (name "unconnected-(U$7-MCU_ERASE-Pad25)") (class "Default")
      (node (ref "U$7") (pin "25") (pinfunction "MCU_ERASE_25") (pintype "input"))
    )
    (net (code "95") (name "unconnected-(U$7-OSC_32K_OUT-Pad10)") (class "Default")
      (node (ref "U$7") (pin "10") (pinfunction "OSC_32K_OUT_10") (pintype "output"))
    )
  )
)
